# Encoders.net
KiCad netlist of a schematic drawn in EAGLE
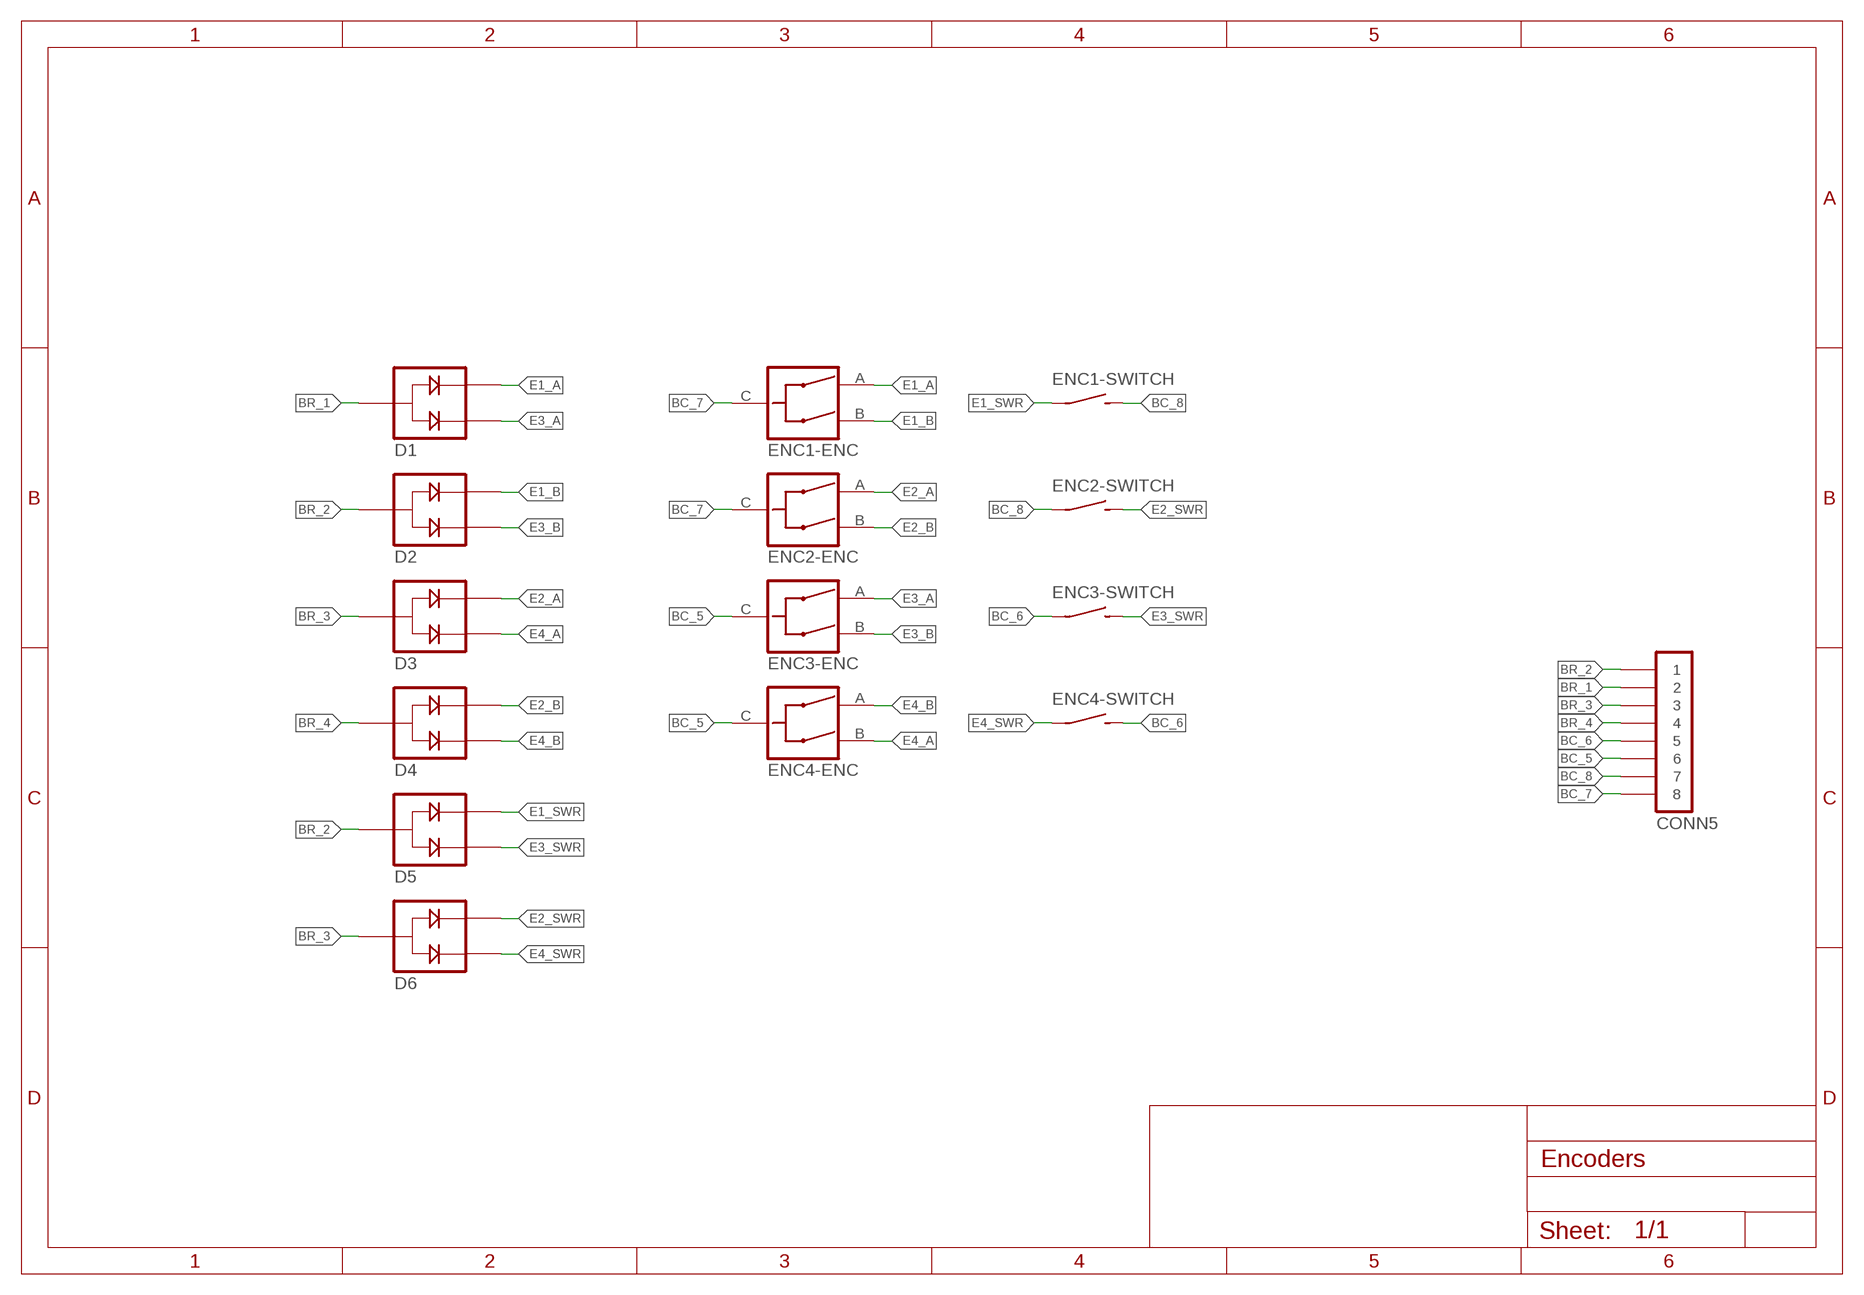
[diagram p0: schematic, sheet 1]

(export (version "E")
  (design (tool "Eeschema 10.0.6"))
  (components
    (comp (ref "CONN5")
      (value "PINHD-1X08-FFC-1MM")
      (footprint "eagle-import:MOLEX-52793-0870")
      (libsource (lib "eagle-import") (part "PINHD-1X08-FFC-1MM"))
    )
    (comp (ref "D1")
      (value "BAW56")
      (footprint "eagle-import:SOT23")
      (fields (field (name "MANUFACTURER") "Multicomp") (field (name "MPN") "BAW56-7-F"))
      (libsource (lib "eagle-import") (part "BAW56"))
    )
    (comp (ref "D2")
      (value "BAW56")
      (footprint "eagle-import:SOT23")
      (fields (field (name "MANUFACTURER") "Multicomp") (field (name "MPN") "BAW56-7-F"))
      (libsource (lib "eagle-import") (part "BAW56"))
    )
    (comp (ref "D3")
      (value "BAW56")
      (footprint "eagle-import:SOT23")
      (fields (field (name "MANUFACTURER") "Multicomp") (field (name "MPN") "BAW56-7-F"))
      (libsource (lib "eagle-import") (part "BAW56"))
    )
    (comp (ref "D4")
      (value "BAW56")
      (footprint "eagle-import:SOT23")
      (fields (field (name "MANUFACTURER") "Multicomp") (field (name "MPN") "BAW56-7-F"))
      (libsource (lib "eagle-import") (part "BAW56"))
    )
    (comp (ref "D5")
      (value "BAW56")
      (footprint "eagle-import:SOT23")
      (fields (field (name "MANUFACTURER") "Multicomp") (field (name "MPN") "BAW56-7-F"))
      (libsource (lib "eagle-import") (part "BAW56"))
    )
    (comp (ref "D6")
      (value "BAW56")
      (footprint "eagle-import:SOT23")
      (fields (field (name "MANUFACTURER") "Multicomp") (field (name "MPN") "BAW56-7-F"))
      (libsource (lib "eagle-import") (part "BAW56"))
    )
    (comp (ref "ENC1")
      (value "BOURNS-PEC12R-4XXXF-SXXXX")
      (footprint "eagle-import:PEC12R-42XXF-S0024")
      (libsource (lib "eagle-import") (part "BOURNS-PEC12R-4XXXF-SXXXX"))
    )
    (comp (ref "ENC2")
      (value "BOURNS-PEC12R-4XXXF-SXXXX")
      (footprint "eagle-import:PEC12R-42XXF-S0024")
      (libsource (lib "eagle-import") (part "BOURNS-PEC12R-4XXXF-SXXXX"))
    )
    (comp (ref "ENC3")
      (value "BOURNS-PEC12R-4XXXF-SXXXX")
      (footprint "eagle-import:PEC12R-42XXF-S0024")
      (libsource (lib "eagle-import") (part "BOURNS-PEC12R-4XXXF-SXXXX"))
    )
    (comp (ref "ENC4")
      (value "BOURNS-PEC12R-4XXXF-SXXXX")
      (footprint "eagle-import:PEC12R-42XXF-S0024")
      (libsource (lib "eagle-import") (part "BOURNS-PEC12R-4XXXF-SXXXX"))
    )
  )
  (nets
    (net (code "1") (name "BC_5") (class "Default")
      (node (ref "CONN5") (pin "6") (pinfunction "6_6") (pintype "passive"))
      (node (ref "ENC3") (pin "C") (pinfunction "C_C") (pintype "input"))
      (node (ref "ENC4") (pin "C") (pinfunction "C_C") (pintype "input"))
    )
    (net (code "2") (name "BC_6") (class "Default")
      (node (ref "CONN5") (pin "5") (pinfunction "5_5") (pintype "passive"))
      (node (ref "ENC3") (pin "SW1") (pinfunction "1_SW1") (pintype "passive"))
      (node (ref "ENC4") (pin "SW2") (pinfunction "2_SW2") (pintype "passive"))
    )
    (net (code "3") (name "BC_7") (class "Default")
      (node (ref "CONN5") (pin "8") (pinfunction "8_8") (pintype "passive"))
      (node (ref "ENC1") (pin "C") (pinfunction "C_C") (pintype "input"))
      (node (ref "ENC2") (pin "C") (pinfunction "C_C") (pintype "input"))
    )
    (net (code "4") (name "BC_8") (class "Default")
      (node (ref "CONN5") (pin "7") (pinfunction "7_7") (pintype "passive"))
      (node (ref "ENC1") (pin "SW2") (pinfunction "2_SW2") (pintype "passive"))
      (node (ref "ENC2") (pin "SW1") (pinfunction "1_SW1") (pintype "passive"))
    )
    (net (code "5") (name "BR_1") (class "Default")
      (node (ref "CONN5") (pin "2") (pinfunction "2_2") (pintype "passive"))
      (node (ref "D1") (pin "3") (pinfunction "3_3") (pintype "passive"))
    )
    (net (code "6") (name "BR_2") (class "Default")
      (node (ref "CONN5") (pin "1") (pinfunction "1_1") (pintype "passive"))
      (node (ref "D2") (pin "3") (pinfunction "3_3") (pintype "passive"))
      (node (ref "D5") (pin "3") (pinfunction "3_3") (pintype "passive"))
    )
    (net (code "7") (name "BR_3") (class "Default")
      (node (ref "CONN5") (pin "3") (pinfunction "3_3") (pintype "passive"))
      (node (ref "D3") (pin "3") (pinfunction "3_3") (pintype "passive"))
      (node (ref "D6") (pin "3") (pinfunction "3_3") (pintype "passive"))
    )
    (net (code "8") (name "BR_4") (class "Default")
      (node (ref "CONN5") (pin "4") (pinfunction "4_4") (pintype "passive"))
      (node (ref "D4") (pin "3") (pinfunction "3_3") (pintype "passive"))
    )
    (net (code "9") (name "E1_A") (class "Default")
      (node (ref "D1") (pin "2") (pinfunction "2_2") (pintype "passive"))
      (node (ref "ENC1") (pin "A") (pinfunction "A_A") (pintype "output"))
    )
    (net (code "10") (name "E1_B") (class "Default")
      (node (ref "D2") (pin "2") (pinfunction "2_2") (pintype "passive"))
      (node (ref "ENC1") (pin "B") (pinfunction "B_B") (pintype "output"))
    )
    (net (code "11") (name "E1_SWR") (class "Default")
      (node (ref "D5") (pin "2") (pinfunction "2_2") (pintype "passive"))
      (node (ref "ENC1") (pin "SW1") (pinfunction "1_SW1") (pintype "passive"))
    )
    (net (code "12") (name "E2_A") (class "Default")
      (node (ref "D3") (pin "2") (pinfunction "2_2") (pintype "passive"))
      (node (ref "ENC2") (pin "A") (pinfunction "A_A") (pintype "output"))
    )
    (net (code "13") (name "E2_B") (class "Default")
      (node (ref "D4") (pin "2") (pinfunction "2_2") (pintype "passive"))
      (node (ref "ENC2") (pin "B") (pinfunction "B_B") (pintype "output"))
    )
    (net (code "14") (name "E2_SWR") (class "Default")
      (node (ref "D6") (pin "2") (pinfunction "2_2") (pintype "passive"))
      (node (ref "ENC2") (pin "SW2") (pinfunction "2_SW2") (pintype "passive"))
    )
    (net (code "15") (name "E3_A") (class "Default")
      (node (ref "D1") (pin "1") (pinfunction "1_1") (pintype "passive"))
      (node (ref "ENC3") (pin "A") (pinfunction "A_A") (pintype "output"))
    )
    (net (code "16") (name "E3_B") (class "Default")
      (node (ref "D2") (pin "1") (pinfunction "1_1") (pintype "passive"))
      (node (ref "ENC3") (pin "B") (pinfunction "B_B") (pintype "output"))
    )
    (net (code "17") (name "E3_SWR") (class "Default")
      (node (ref "D5") (pin "1") (pinfunction "1_1") (pintype "passive"))
      (node (ref "ENC3") (pin "SW2") (pinfunction "2_SW2") (pintype "passive"))
    )
    (net (code "18") (name "E4_A") (class "Default")
      (node (ref "D3") (pin "1") (pinfunction "1_1") (pintype "passive"))
      (node (ref "ENC4") (pin "B") (pinfunction "B_B") (pintype "output"))
    )
    (net (code "19") (name "E4_B") (class "Default")
      (node (ref "D4") (pin "1") (pinfunction "1_1") (pintype "passive"))
      (node (ref "ENC4") (pin "A") (pinfunction "A_A") (pintype "output"))
    )
    (net (code "20") (name "E4_SWR") (class "Default")
      (node (ref "D6") (pin "1") (pinfunction "1_1") (pintype "passive"))
      (node (ref "ENC4") (pin "SW1") (pinfunction "1_SW1") (pintype "passive"))
    )
  )
)
